# Microcontroller.net
KiCad netlist of a schematic drawn in Altium Designer
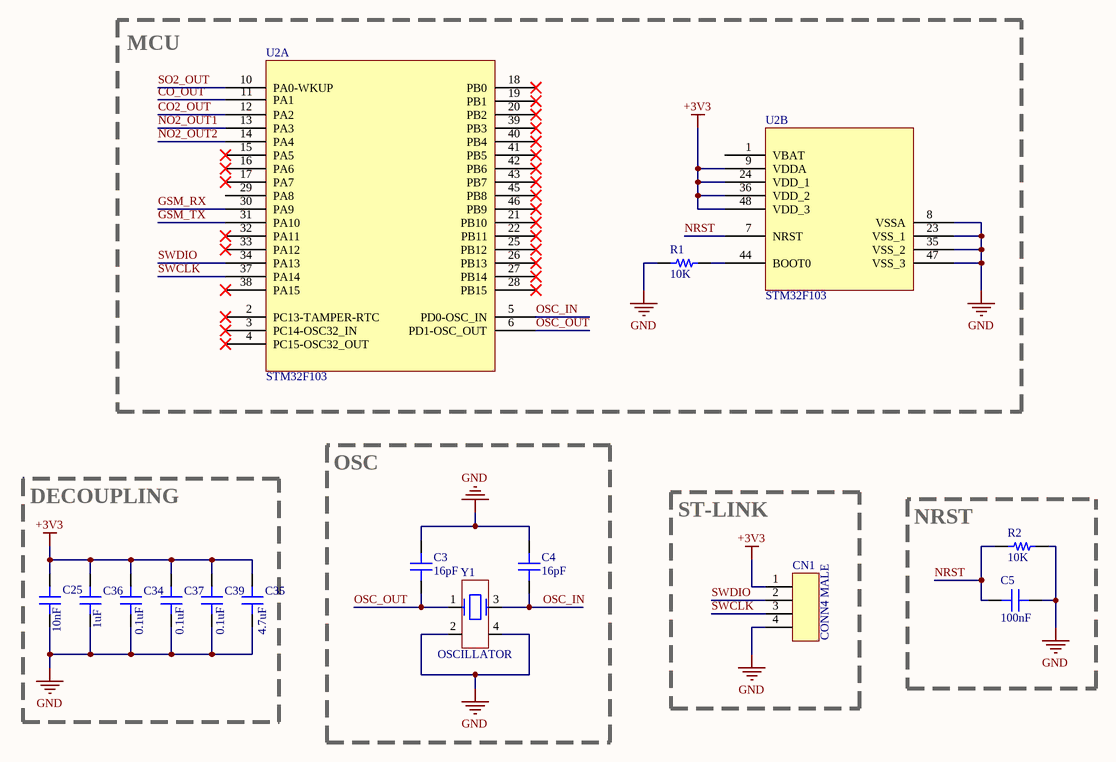
[diagram p0: Microcontroller.SchDoc]

(export (version "E")
  (design (tool "Eeschema 10.0.6"))
  (components
    (comp (ref "C3")
      (value "16pF")
      (footprint "CAP 0603_1608")
      (description "CERAMİC 1206 SMD")
      (libsource (lib "hava_kalitesi_olcumu") (part "16pF"))
    )
    (comp (ref "C4")
      (value "16pF")
      (footprint "CAP 0603_1608")
      (description "CERAMİC 1206 SMD")
      (libsource (lib "hava_kalitesi_olcumu") (part "16pF"))
    )
    (comp (ref "C5")
      (value "100nF")
      (footprint "CAP 0603_1608")
      (description "CERAMİC 1206 SMD")
      (libsource (lib "hava_kalitesi_olcumu") (part "100nF"))
    )
    (comp (ref "C25")
      (value "10nF")
      (footprint "CAP 0603_1608")
      (description "CERAMİC 1206 SMD")
      (libsource (lib "hava_kalitesi_olcumu") (part "10nF"))
    )
    (comp (ref "C34")
      (value "0.1uF")
      (footprint "CAP 0603_1608")
      (description "CERAMİC 1206 SMD")
      (libsource (lib "hava_kalitesi_olcumu") (part "0.1uF"))
    )
    (comp (ref "C35")
      (value "4.7uF")
      (footprint "CAP 0603_1608")
      (description "CERAMİC 1206 SMD")
      (libsource (lib "hava_kalitesi_olcumu") (part "4.7uF"))
    )
    (comp (ref "C36")
      (value "1uF")
      (footprint "CAP 0603_1608")
      (description "CERAMİC 1206 SMD")
      (libsource (lib "hava_kalitesi_olcumu") (part "1uF"))
    )
    (comp (ref "C37")
      (value "0.1uF")
      (footprint "CAP 0603_1608")
      (description "CERAMİC 1206 SMD")
      (libsource (lib "hava_kalitesi_olcumu") (part "0.1uF"))
    )
    (comp (ref "C39")
      (value "0.1uF")
      (footprint "CAP 0603_1608")
      (description "CERAMİC 1206 SMD")
      (libsource (lib "hava_kalitesi_olcumu") (part "0.1uF"))
    )
    (comp (ref "CN1")
      (value "CONN4 MALE")
      (footprint "CONN4 MALE")
      (description "4 PIN 2.54MM")
      (libsource (lib "hava_kalitesi_olcumu") (part "CONN4 MALE"))
    )
    (comp (ref "R1")
      (value "10K")
      (footprint "RES 0603_1608")
      (description "SMT RES 1206")
      (libsource (lib "hava_kalitesi_olcumu") (part "10K"))
    )
    (comp (ref "R2")
      (value "10K")
      (footprint "RES 0603_1608")
      (description "SMT RES 1206")
      (libsource (lib "hava_kalitesi_olcumu") (part "10K"))
    )
    (comp (ref "U2")
      (value "STM32F103")
      (footprint "LQFP48")
      (description "STM32F103C8T6 SMD LQFP-48 32-Bit 72 MHz Mikrodenetleyici")
      (libsource (lib "hava_kalitesi_olcumu") (part "STM32F103"))
    )
    (comp (ref "Y1")
      (value "OSCILLATOR")
      (footprint "OSCILLATOR")
      (description "8MHZ 12.5pF")
      (libsource (lib "hava_kalitesi_olcumu") (part "OSCILLATOR"))
    )
  )
  (nets
    (net (code "1") (name "+3V3") (class "Default")
      (node (ref "C25") (pin "2") (pinfunction "2_2") (pintype "passive"))
      (node (ref "C34") (pin "2") (pinfunction "2_2") (pintype "passive"))
      (node (ref "C35") (pin "2") (pinfunction "2_2") (pintype "passive"))
      (node (ref "C36") (pin "2") (pinfunction "2_2") (pintype "passive"))
      (node (ref "C37") (pin "2") (pinfunction "2_2") (pintype "passive"))
      (node (ref "C39") (pin "2") (pinfunction "2_2") (pintype "passive"))
      (node (ref "CN1") (pin "1") (pintype "passive"))
      (node (ref "U2") (pin "24") (pinfunction "VDD_1_24") (pintype "passive"))
      (node (ref "U2") (pin "36") (pinfunction "VDD_2_36") (pintype "passive"))
      (node (ref "U2") (pin "48") (pinfunction "VDD_3_48") (pintype "passive"))
      (node (ref "U2") (pin "9") (pinfunction "VDDA_9") (pintype "passive"))
    )
    (net (code "2") (name "/CO2_OUT") (class "Default")
      (node (ref "U2") (pin "12") (pinfunction "PA2_12") (pintype "passive"))
    )
    (net (code "3") (name "/CO_OUT") (class "Default")
      (node (ref "U2") (pin "11") (pinfunction "PA1_11") (pintype "passive"))
    )
    (net (code "4") (name "/GSM_RX") (class "Default")
      (node (ref "U2") (pin "30") (pinfunction "PA9_30") (pintype "passive"))
    )
    (net (code "5") (name "/GSM_TX") (class "Default")
      (node (ref "U2") (pin "31") (pinfunction "PA10_31") (pintype "passive"))
    )
    (net (code "6") (name "/NO2_OUT1") (class "Default")
      (node (ref "U2") (pin "13") (pinfunction "PA3_13") (pintype "passive"))
    )
    (net (code "7") (name "/NO2_OUT2") (class "Default")
      (node (ref "U2") (pin "14") (pinfunction "PA4_14") (pintype "passive"))
    )
    (net (code "8") (name "/NRST") (class "Default")
      (node (ref "C5") (pin "2") (pinfunction "2_2") (pintype "passive"))
      (node (ref "R2") (pin "1") (pinfunction "1_1") (pintype "passive"))
      (node (ref "U2") (pin "7") (pinfunction "NRST_7") (pintype "passive"))
    )
    (net (code "9") (name "/OSC_IN") (class "Default")
      (node (ref "C4") (pin "1") (pinfunction "1_1") (pintype "passive"))
      (node (ref "U2") (pin "5") (pinfunction "PD0-OSC_IN_5") (pintype "passive"))
      (node (ref "Y1") (pin "3") (pinfunction "3_3") (pintype "passive"))
    )
    (net (code "10") (name "/OSC_OUT") (class "Default")
      (node (ref "C3") (pin "1") (pinfunction "1_1") (pintype "passive"))
      (node (ref "U2") (pin "6") (pinfunction "PD1-OSC_OUT_6") (pintype "passive"))
      (node (ref "Y1") (pin "1") (pinfunction "1_1") (pintype "passive"))
    )
    (net (code "11") (name "/SO2_OUT") (class "Default")
      (node (ref "U2") (pin "10") (pinfunction "PA0-WKUP_10") (pintype "passive"))
    )
    (net (code "12") (name "/SWCLK") (class "Default")
      (node (ref "CN1") (pin "3") (pintype "passive"))
      (node (ref "U2") (pin "37") (pinfunction "PA14_37") (pintype "passive"))
    )
    (net (code "13") (name "/SWDIO") (class "Default")
      (node (ref "CN1") (pin "2") (pintype "passive"))
      (node (ref "U2") (pin "34") (pinfunction "PA13_34") (pintype "passive"))
    )
    (net (code "14") (name "GND") (class "Default")
      (node (ref "C25") (pin "1") (pinfunction "1_1") (pintype "passive"))
      (node (ref "C3") (pin "2") (pinfunction "2_2") (pintype "passive"))
      (node (ref "C34") (pin "1") (pinfunction "1_1") (pintype "passive"))
      (node (ref "C35") (pin "1") (pinfunction "1_1") (pintype "passive"))
      (node (ref "C36") (pin "1") (pinfunction "1_1") (pintype "passive"))
      (node (ref "C37") (pin "1") (pinfunction "1_1") (pintype "passive"))
      (node (ref "C39") (pin "1") (pinfunction "1_1") (pintype "passive"))
      (node (ref "C4") (pin "2") (pinfunction "2_2") (pintype "passive"))
      (node (ref "C5") (pin "1") (pinfunction "1_1") (pintype "passive"))
      (node (ref "CN1") (pin "4") (pintype "passive"))
      (node (ref "R1") (pin "1") (pinfunction "1_1") (pintype "passive"))
      (node (ref "R2") (pin "2") (pinfunction "2_2") (pintype "passive"))
      (node (ref "U2") (pin "23") (pinfunction "VSS_1_23") (pintype "passive"))
      (node (ref "U2") (pin "35") (pinfunction "VSS_2_35") (pintype "passive"))
      (node (ref "U2") (pin "47") (pinfunction "VSS_3_47") (pintype "passive"))
      (node (ref "U2") (pin "8") (pinfunction "VSSA_8") (pintype "passive"))
      (node (ref "Y1") (pin "2") (pinfunction "2_2") (pintype "passive"))
      (node (ref "Y1") (pin "4") (pinfunction "4_4") (pintype "passive"))
    )
    (net (code "15") (name "Net-(U2B-BOOT0)") (class "Default")
      (node (ref "R1") (pin "2") (pinfunction "2_2") (pintype "passive"))
      (node (ref "U2") (pin "44") (pinfunction "BOOT0_44") (pintype "passive"))
    )
    (net (code "16") (name "unconnected-(U2A-PA1-Pad11)") (class "Default")
      (node (ref "U2") (pin "11") (pinfunction "PA1_11") (pintype "passive"))
    )
    (net (code "17") (name "unconnected-(U2A-PA5-Pad15)") (class "Default")
      (node (ref "U2") (pin "15") (pinfunction "PA5_15") (pintype "passive+no_connect"))
    )
    (net (code "18") (name "unconnected-(U2A-PA6-Pad16)") (class "Default")
      (node (ref "U2") (pin "16") (pinfunction "PA6_16") (pintype "passive+no_connect"))
    )
    (net (code "19") (name "unconnected-(U2A-PA7-Pad17)") (class "Default")
      (node (ref "U2") (pin "17") (pinfunction "PA7_17") (pintype "passive+no_connect"))
    )
    (net (code "20") (name "unconnected-(U2A-PA8-Pad29)") (class "Default")
      (node (ref "U2") (pin "29") (pinfunction "PA8_29") (pintype "passive"))
    )
    (net (code "21") (name "unconnected-(U2A-PA11-Pad32)") (class "Default")
      (node (ref "U2") (pin "32") (pinfunction "PA11_32") (pintype "passive+no_connect"))
    )
    (net (code "22") (name "unconnected-(U2A-PA12-Pad33)") (class "Default")
      (node (ref "U2") (pin "33") (pinfunction "PA12_33") (pintype "passive+no_connect"))
    )
    (net (code "23") (name "unconnected-(U2A-PA15-Pad38)") (class "Default")
      (node (ref "U2") (pin "38") (pinfunction "PA15_38") (pintype "passive+no_connect"))
    )
    (net (code "24") (name "unconnected-(U2A-PB0-Pad18)") (class "Default")
      (node (ref "U2") (pin "18") (pinfunction "PB0_18") (pintype "passive+no_connect"))
    )
    (net (code "25") (name "unconnected-(U2A-PB1-Pad19)") (class "Default")
      (node (ref "U2") (pin "19") (pinfunction "PB1_19") (pintype "passive+no_connect"))
    )
    (net (code "26") (name "unconnected-(U2A-PB2-Pad20)") (class "Default")
      (node (ref "U2") (pin "20") (pinfunction "PB2_20") (pintype "passive+no_connect"))
    )
    (net (code "27") (name "unconnected-(U2A-PB3-Pad39)") (class "Default")
      (node (ref "U2") (pin "39") (pinfunction "PB3_39") (pintype "passive+no_connect"))
    )
    (net (code "28") (name "unconnected-(U2A-PB4-Pad40)") (class "Default")
      (node (ref "U2") (pin "40") (pinfunction "PB4_40") (pintype "passive+no_connect"))
    )
    (net (code "29") (name "unconnected-(U2A-PB5-Pad41)") (class "Default")
      (node (ref "U2") (pin "41") (pinfunction "PB5_41") (pintype "passive+no_connect"))
    )
    (net (code "30") (name "unconnected-(U2A-PB6-Pad42)") (class "Default")
      (node (ref "U2") (pin "42") (pinfunction "PB6_42") (pintype "passive+no_connect"))
    )
    (net (code "31") (name "unconnected-(U2A-PB7-Pad43)") (class "Default")
      (node (ref "U2") (pin "43") (pinfunction "PB7_43") (pintype "passive+no_connect"))
    )
    (net (code "32") (name "unconnected-(U2A-PB8-Pad45)") (class "Default")
      (node (ref "U2") (pin "45") (pinfunction "PB8_45") (pintype "passive+no_connect"))
    )
    (net (code "33") (name "unconnected-(U2A-PB9-Pad46)") (class "Default")
      (node (ref "U2") (pin "46") (pinfunction "PB9_46") (pintype "passive+no_connect"))
    )
    (net (code "34") (name "unconnected-(U2A-PB10-Pad21)") (class "Default")
      (node (ref "U2") (pin "21") (pinfunction "PB10_21") (pintype "passive+no_connect"))
    )
    (net (code "35") (name "unconnected-(U2A-PB11-Pad22)") (class "Default")
      (node (ref "U2") (pin "22") (pinfunction "PB11_22") (pintype "passive+no_connect"))
    )
    (net (code "36") (name "unconnected-(U2A-PB12-Pad25)") (class "Default")
      (node (ref "U2") (pin "25") (pinfunction "PB12_25") (pintype "passive+no_connect"))
    )
    (net (code "37") (name "unconnected-(U2A-PB13-Pad26)") (class "Default")
      (node (ref "U2") (pin "26") (pinfunction "PB13_26") (pintype "passive+no_connect"))
    )
    (net (code "38") (name "unconnected-(U2A-PB14-Pad27)") (class "Default")
      (node (ref "U2") (pin "27") (pinfunction "PB14_27") (pintype "passive+no_connect"))
    )
    (net (code "39") (name "unconnected-(U2A-PB15-Pad28)") (class "Default")
      (node (ref "U2") (pin "28") (pinfunction "PB15_28") (pintype "passive+no_connect"))
    )
    (net (code "40") (name "unconnected-(U2A-PC13-TAMPER-RTC-Pad2)") (class "Default")
      (node (ref "U2") (pin "2") (pinfunction "PC13-TAMPER-RTC_2") (pintype "passive+no_connect"))
    )
    (net (code "41") (name "unconnected-(U2A-PC14-OSC32_IN-Pad3)") (class "Default")
      (node (ref "U2") (pin "3") (pinfunction "PC14-OSC32_IN_3") (pintype "passive+no_connect"))
    )
    (net (code "42") (name "unconnected-(U2A-PC15-OSC32_OUT-Pad4)") (class "Default")
      (node (ref "U2") (pin "4") (pinfunction "PC15-OSC32_OUT_4") (pintype "passive+no_connect"))
    )
    (net (code "43") (name "unconnected-(U2B-VBAT-Pad1)") (class "Default")
      (node (ref "U2") (pin "1") (pinfunction "VBAT_1") (pintype "passive"))
    )
  )
)
